# Blaster.net
KiCad netlist of a schematic drawn in EasyEDA Pro
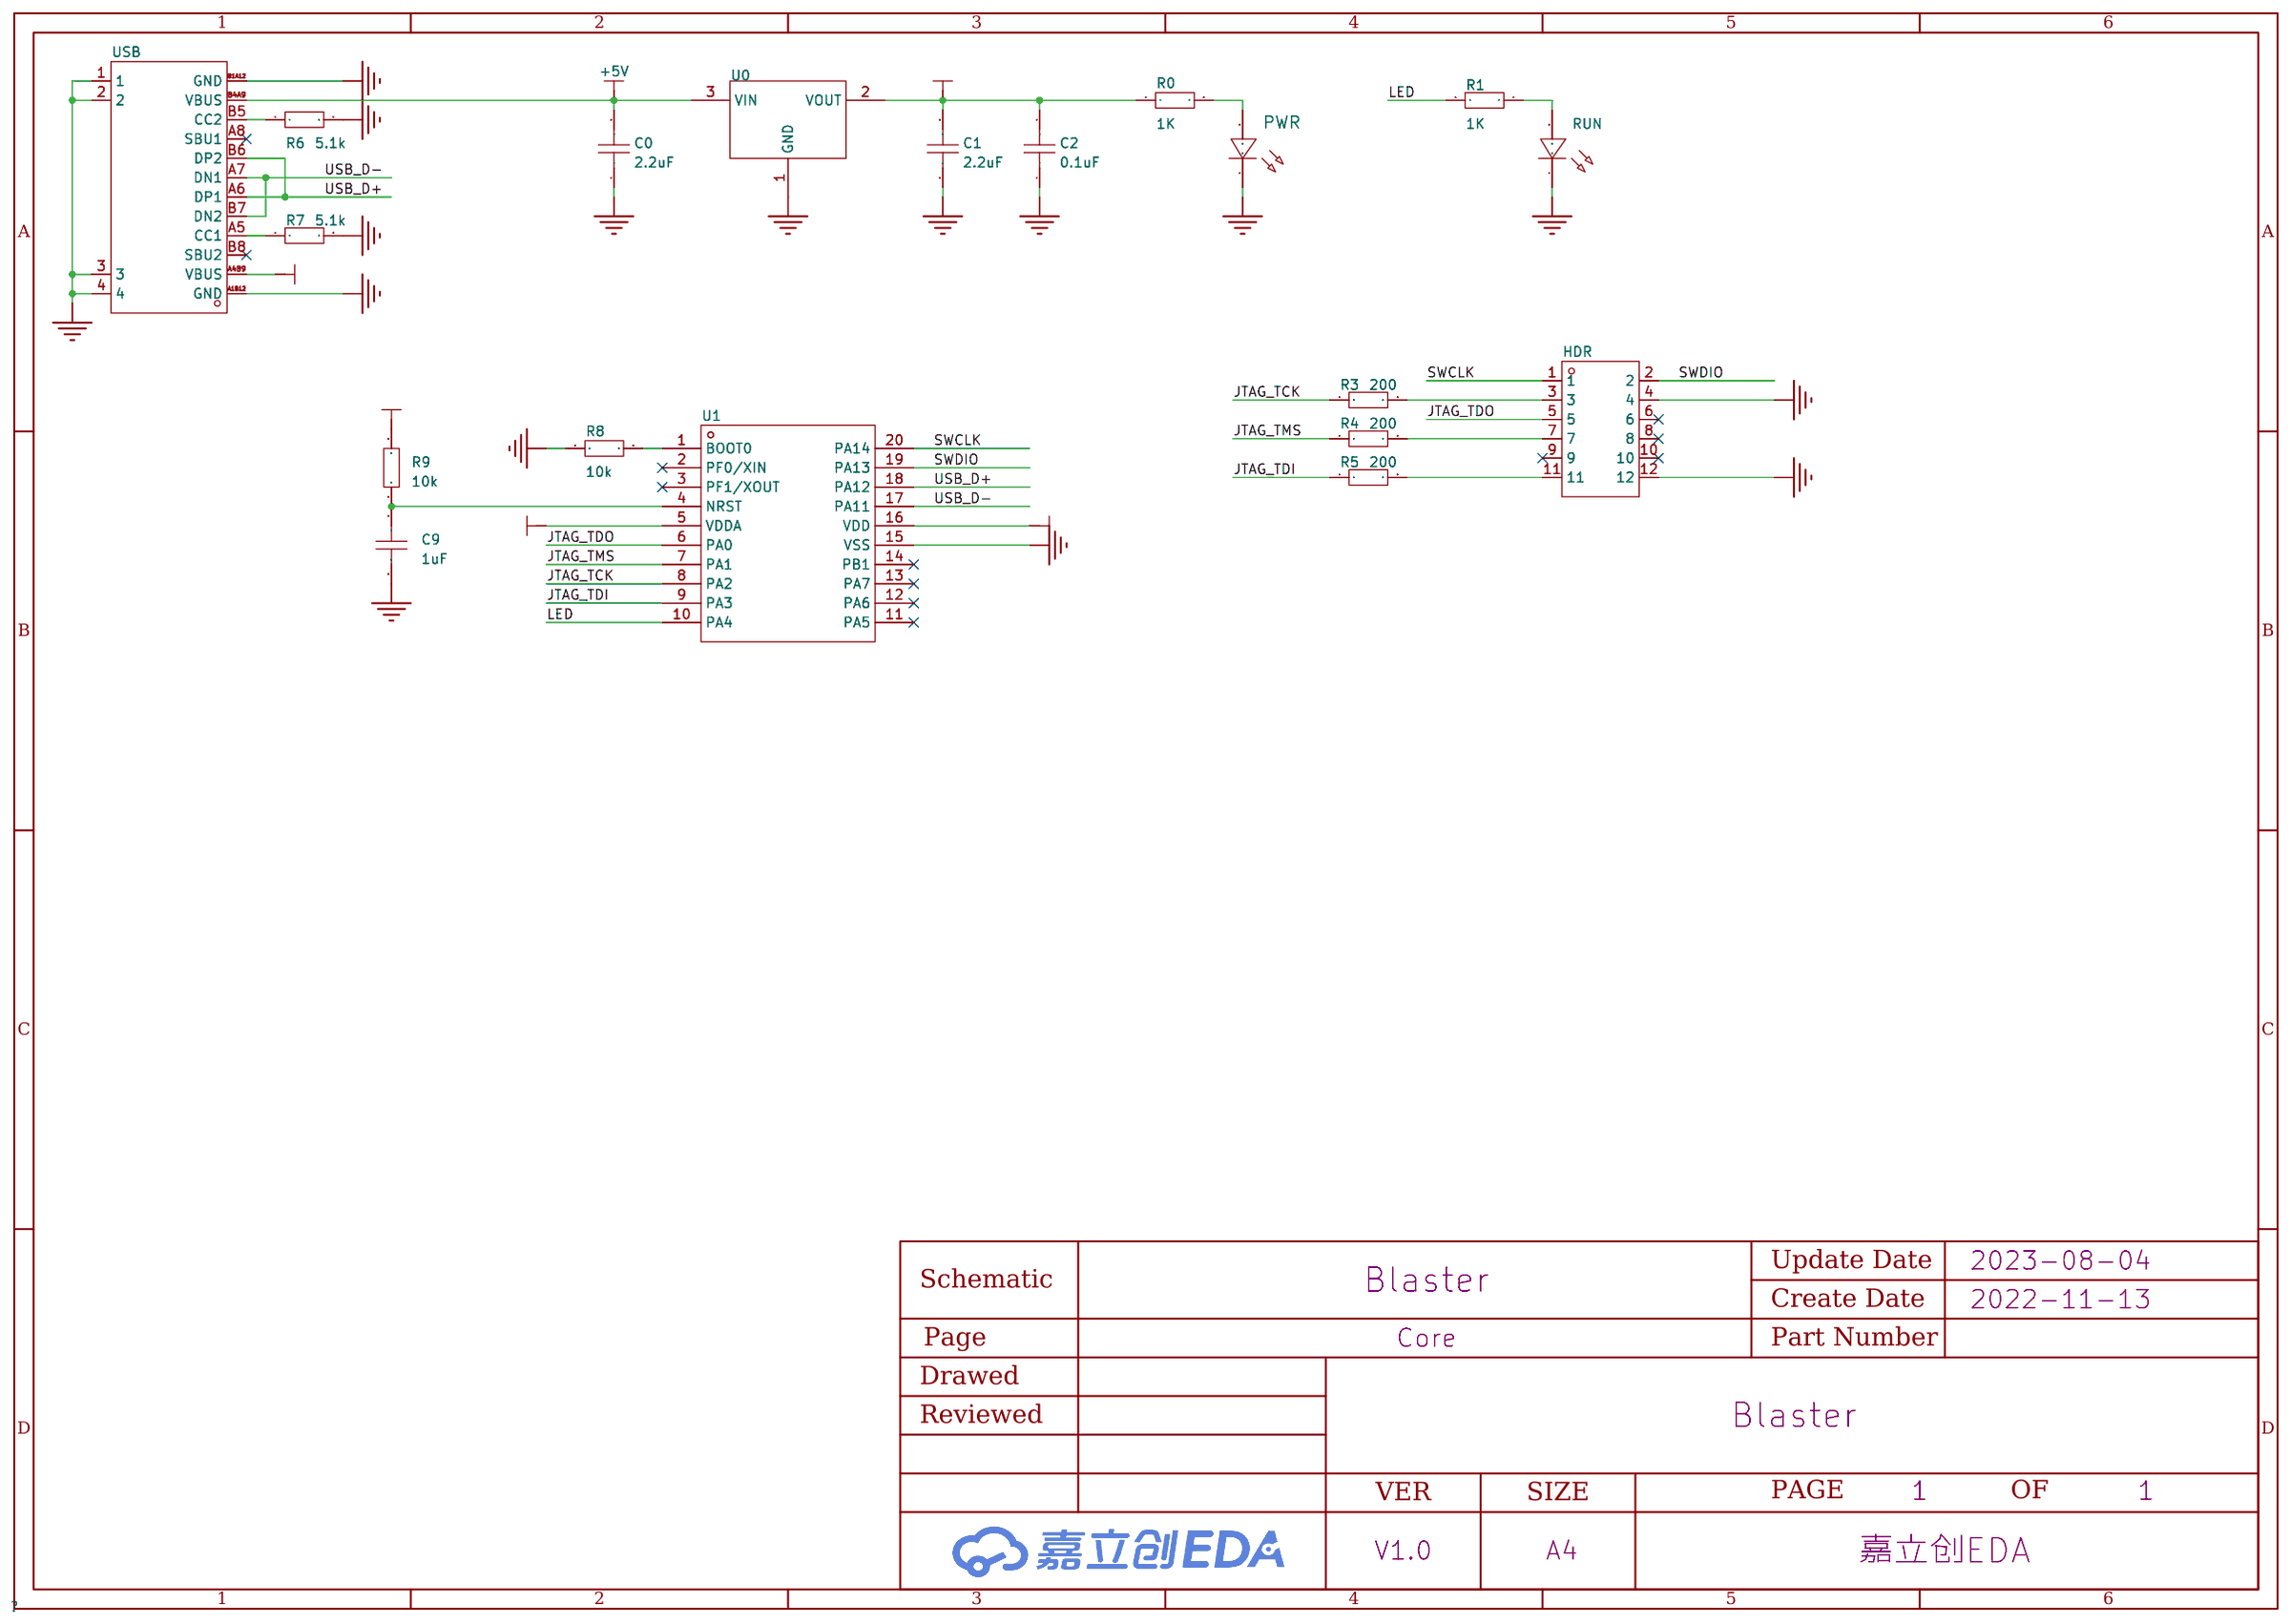
[diagram p0: schematic sheet]

(export (version "E")
  (design (tool "Eeschema 10.0.6"))
  (components
    (comp (ref "C0")
      (value "2.2uF")
      (footprint "easyedapro:C0603")
      (description "容值:100nF;精度:±10%;额定电压:50V;温度系数:X7R;")
      (libsource (lib "easyedapro") (part "C1210X7R475K630NT"))
    )
    (comp (ref "C1")
      (value "2.2uF")
      (footprint "easyedapro:C0603")
      (description "容值:100nF;精度:±10%;额定电压:50V;温度系数:X7R;")
      (libsource (lib "easyedapro") (part "C1210X7R475K630NT"))
    )
    (comp (ref "C2")
      (value "0.1uF")
      (footprint "easyedapro:C0603")
      (description "容值:100nF;精度:±10%;额定电压:50V;温度系数:X7R;")
      (libsource (lib "easyedapro") (part "C1210X7R475K630NT"))
    )
    (comp (ref "C9")
      (value "1uF")
      (footprint "easyedapro:C0603")
      (description "容值:100nF;精度:±10%;额定电压:50V;温度系数:X7R;")
      (libsource (lib "easyedapro") (part "C1210X7R475K630NT"))
    )
    (comp (ref "HDR")
      (value "~")
      (footprint "easyedapro:HDR-SMD_2X6P-P2.54")
      (libsource (lib "easyedapro") (part "HDR-M-2.54_2x6"))
    )
    (comp (ref "PWR")
      (value "~")
      (footprint "easyedapro:LED0603-RD_BLUE")
      (libsource (lib "easyedapro") (part "LED_R"))
    )
    (comp (ref "R0") (value "1K") (footprint "easyedapro:R0603") (libsource (lib "easyedapro") (part "电阻")))
    (comp (ref "R1") (value "1K") (footprint "easyedapro:R0603") (libsource (lib "easyedapro") (part "电阻")))
    (comp (ref "R3") (value "200") (footprint "easyedapro:R0603") (libsource (lib "easyedapro") (part "电阻")))
    (comp (ref "R4") (value "200") (footprint "easyedapro:R0603") (libsource (lib "easyedapro") (part "电阻")))
    (comp (ref "R5") (value "200") (footprint "easyedapro:R0603") (libsource (lib "easyedapro") (part "电阻")))
    (comp (ref "R6") (value "5.1k") (footprint "easyedapro:R0603") (libsource (lib "easyedapro") (part "电阻")))
    (comp (ref "R7") (value "5.1k") (footprint "easyedapro:R0603") (libsource (lib "easyedapro") (part "电阻")))
    (comp (ref "R8") (value "10k") (footprint "easyedapro:R0603") (libsource (lib "easyedapro") (part "电阻")))
    (comp (ref "R9") (value "10k") (footprint "easyedapro:R0603") (libsource (lib "easyedapro") (part "电阻")))
    (comp (ref "RUN")
      (value "~")
      (footprint "easyedapro:LED0603-RD")
      (description "照明颜色:翠绿;色温 - CCT（K）:-;主波长/色坐标:520~535nm;")
      (libsource (lib "easyedapro") (part "LED_G"))
    )
    (comp (ref "U0")
      (value "HT7233")
      (footprint "easyedapro:SOT-23-3_L2.9-W1.6-P1.90-LS2.8-BR")
      (fields (field (name "Manufacturer") "HOLTEK(台湾合泰/盛群)"))
      (libsource (lib "easyedapro") (part "HT7233"))
    )
    (comp (ref "U1")
      (value "~")
      (footprint "easyedapro:TSSOP-20_L6.5-W4.4-P0.65-LS6.4-BL")
      (libsource (lib "easyedapro") (part "AT32F425F8"))
    )
    (comp (ref "USB")
      (value "USB-TYPE-C-017")
      (footprint "easyedapro:USB-TYPE-C-SMD_C9900008089")
      (description "连接器类型:Type-C;标准:-;公母:母座;触点数量:16;端口数量:1;安装方式:卧贴;额定电流 - 电源:3A;工作温度范围:-25~+85;")
      (fields (field (name "Manufacturer") "DEALON(德艺隆)"))
      (libsource (lib "easyedapro") (part "USB-TYPE-C-017"))
    )
  )
  (nets
    (net (code "1") (name "+3.3V") (class "Default")
      (node (ref "C1") (pin "2") (pinfunction "2_2") (pintype "input"))
      (node (ref "C2") (pin "2") (pinfunction "2_2") (pintype "input"))
      (node (ref "R0") (pin "1") (pinfunction "1_1") (pintype "input"))
      (node (ref "R9") (pin "2") (pinfunction "2_2") (pintype "input"))
      (node (ref "U0") (pin "2") (pinfunction "VOUT_2") (pintype "input"))
      (node (ref "U1") (pin "16") (pinfunction "VDD_16") (pintype "input"))
      (node (ref "U1") (pin "5") (pinfunction "VDDA_5") (pintype "input"))
    )
    (net (code "2") (name "+5V") (class "Default")
      (node (ref "C0") (pin "2") (pinfunction "2_2") (pintype "input"))
      (node (ref "U0") (pin "3") (pinfunction "VIN_3") (pintype "input"))
      (node (ref "USB") (pin "A4B9") (pinfunction "VBUS_A4B9") (pintype "input"))
      (node (ref "USB") (pin "B4A9") (pinfunction "VBUS_B4A9") (pintype "input"))
    )
    (net (code "3") (name "/JTAG_TCK") (class "Default")
      (node (ref "R3") (pin "1") (pinfunction "1_1") (pintype "input"))
      (node (ref "U1") (pin "8") (pinfunction "PA2_8") (pintype "input"))
    )
    (net (code "4") (name "/JTAG_TDI") (class "Default")
      (node (ref "R5") (pin "1") (pinfunction "1_1") (pintype "input"))
      (node (ref "U1") (pin "9") (pinfunction "PA3_9") (pintype "input"))
    )
    (net (code "5") (name "/JTAG_TDO") (class "Default")
      (node (ref "HDR") (pin "5") (pinfunction "5_5") (pintype "input"))
      (node (ref "U1") (pin "6") (pinfunction "PA0_6") (pintype "input"))
    )
    (net (code "6") (name "/JTAG_TMS") (class "Default")
      (node (ref "R4") (pin "1") (pinfunction "1_1") (pintype "input"))
      (node (ref "U1") (pin "7") (pinfunction "PA1_7") (pintype "input"))
    )
    (net (code "7") (name "/LED") (class "Default")
      (node (ref "R1") (pin "2") (pinfunction "2_2") (pintype "input"))
      (node (ref "U1") (pin "10") (pinfunction "PA4_10") (pintype "input"))
    )
    (net (code "8") (name "/SWCLK") (class "Default")
      (node (ref "HDR") (pin "1") (pinfunction "1_1") (pintype "input"))
      (node (ref "U1") (pin "20") (pinfunction "PA14_20") (pintype "input"))
    )
    (net (code "9") (name "/SWDIO") (class "Default")
      (node (ref "HDR") (pin "2") (pinfunction "2_2") (pintype "input"))
      (node (ref "U1") (pin "19") (pinfunction "PA13_19") (pintype "input"))
    )
    (net (code "10") (name "/USB_D+") (class "Default")
      (node (ref "U1") (pin "18") (pinfunction "PA12_18") (pintype "input"))
      (node (ref "USB") (pin "A6") (pinfunction "DP1_A6") (pintype "input"))
      (node (ref "USB") (pin "B6") (pinfunction "DP2_B6") (pintype "input"))
    )
    (net (code "11") (name "/USB_D-") (class "Default")
      (node (ref "U1") (pin "17") (pinfunction "PA11_17") (pintype "input"))
      (node (ref "USB") (pin "A7") (pinfunction "DN1_A7") (pintype "input"))
      (node (ref "USB") (pin "B7") (pinfunction "DN2_B7") (pintype "input"))
    )
    (net (code "12") (name "GND") (class "Default")
      (node (ref "C0") (pin "1") (pinfunction "1_1") (pintype "input"))
      (node (ref "C1") (pin "1") (pinfunction "1_1") (pintype "input"))
      (node (ref "C2") (pin "1") (pinfunction "1_1") (pintype "input"))
      (node (ref "C9") (pin "2") (pinfunction "2_2") (pintype "input"))
      (node (ref "HDR") (pin "12") (pinfunction "12_12") (pintype "input"))
      (node (ref "HDR") (pin "4") (pinfunction "4_4") (pintype "input"))
      (node (ref "PWR") (pin "1") (pinfunction "C_1") (pintype "input"))
      (node (ref "R6") (pin "2") (pinfunction "2_2") (pintype "input"))
      (node (ref "R7") (pin "2") (pinfunction "2_2") (pintype "input"))
      (node (ref "R8") (pin "1") (pinfunction "1_1") (pintype "input"))
      (node (ref "RUN") (pin "1") (pinfunction "C_1") (pintype "input"))
      (node (ref "U0") (pin "1") (pinfunction "GND_1") (pintype "input"))
      (node (ref "U1") (pin "15") (pinfunction "VSS_15") (pintype "input"))
      (node (ref "USB") (pin "1") (pinfunction "1_1") (pintype "input"))
      (node (ref "USB") (pin "2") (pinfunction "2_2") (pintype "input"))
      (node (ref "USB") (pin "3") (pinfunction "3_3") (pintype "input"))
      (node (ref "USB") (pin "4") (pinfunction "4_4") (pintype "input"))
      (node (ref "USB") (pin "A1B12") (pinfunction "GND_A1B12") (pintype "input"))
      (node (ref "USB") (pin "B1A12") (pinfunction "GND_B1A12") (pintype "input"))
    )
    (net (code "13") (name "Net-(HDR-Pad3)") (class "Default")
      (node (ref "HDR") (pin "3") (pinfunction "3_3") (pintype "input"))
      (node (ref "R3") (pin "2") (pinfunction "2_2") (pintype "input"))
    )
    (net (code "14") (name "Net-(HDR-Pad7)") (class "Default")
      (node (ref "HDR") (pin "7") (pinfunction "7_7") (pintype "input"))
      (node (ref "R4") (pin "2") (pinfunction "2_2") (pintype "input"))
    )
    (net (code "15") (name "Net-(HDR-Pad11)") (class "Default")
      (node (ref "HDR") (pin "11") (pinfunction "11_11") (pintype "input"))
      (node (ref "R5") (pin "2") (pinfunction "2_2") (pintype "input"))
    )
    (net (code "16") (name "Net-(PWR-A)") (class "Default")
      (node (ref "PWR") (pin "2") (pinfunction "A_2") (pintype "input"))
      (node (ref "R0") (pin "2") (pinfunction "2_2") (pintype "input"))
    )
    (net (code "17") (name "Net-(RUN-A)") (class "Default")
      (node (ref "R1") (pin "1") (pinfunction "1_1") (pintype "input"))
      (node (ref "RUN") (pin "2") (pinfunction "A_2") (pintype "input"))
    )
    (net (code "18") (name "Net-(U1-BOOT0)") (class "Default")
      (node (ref "R8") (pin "2") (pinfunction "2_2") (pintype "input"))
      (node (ref "U1") (pin "1") (pinfunction "BOOT0_1") (pintype "input"))
    )
    (net (code "19") (name "Net-(U1-NRST)") (class "Default")
      (node (ref "C9") (pin "1") (pinfunction "1_1") (pintype "input"))
      (node (ref "R9") (pin "1") (pinfunction "1_1") (pintype "input"))
      (node (ref "U1") (pin "4") (pinfunction "NRST_4") (pintype "input"))
    )
    (net (code "20") (name "Net-(USB-CC1)") (class "Default")
      (node (ref "R7") (pin "1") (pinfunction "1_1") (pintype "input"))
      (node (ref "USB") (pin "A5") (pinfunction "CC1_A5") (pintype "input"))
    )
    (net (code "21") (name "Net-(USB-CC2)") (class "Default")
      (node (ref "R6") (pin "1") (pinfunction "1_1") (pintype "input"))
      (node (ref "USB") (pin "B5") (pinfunction "CC2_B5") (pintype "input"))
    )
    (net (code "22") (name "unconnected-(HDR-Pad6)") (class "Default")
      (node (ref "HDR") (pin "6") (pinfunction "6_6") (pintype "input+no_connect"))
    )
    (net (code "23") (name "unconnected-(HDR-Pad8)") (class "Default")
      (node (ref "HDR") (pin "8") (pinfunction "8_8") (pintype "input+no_connect"))
    )
    (net (code "24") (name "unconnected-(HDR-Pad9)") (class "Default")
      (node (ref "HDR") (pin "9") (pinfunction "9_9") (pintype "input+no_connect"))
    )
    (net (code "25") (name "unconnected-(HDR-Pad10)") (class "Default")
      (node (ref "HDR") (pin "10") (pinfunction "10_10") (pintype "input+no_connect"))
    )
    (net (code "26") (name "unconnected-(U1-PA5-Pad11)") (class "Default")
      (node (ref "U1") (pin "11") (pinfunction "PA5_11") (pintype "input+no_connect"))
    )
    (net (code "27") (name "unconnected-(U1-PA6-Pad12)") (class "Default")
      (node (ref "U1") (pin "12") (pinfunction "PA6_12") (pintype "input+no_connect"))
    )
    (net (code "28") (name "unconnected-(U1-PA7-Pad13)") (class "Default")
      (node (ref "U1") (pin "13") (pinfunction "PA7_13") (pintype "input+no_connect"))
    )
    (net (code "29") (name "unconnected-(U1-PB1-Pad14)") (class "Default")
      (node (ref "U1") (pin "14") (pinfunction "PB1_14") (pintype "input+no_connect"))
    )
    (net (code "30") (name "unconnected-(U1-PF0{slash}XIN-Pad2)") (class "Default")
      (node (ref "U1") (pin "2") (pinfunction "PF0/XIN_2") (pintype "input+no_connect"))
    )
    (net (code "31") (name "unconnected-(U1-PF1{slash}XOUT-Pad3)") (class "Default")
      (node (ref "U1") (pin "3") (pinfunction "PF1/XOUT_3") (pintype "input+no_connect"))
    )
    (net (code "32") (name "unconnected-(USB-SBU1-PadA8)") (class "Default")
      (node (ref "USB") (pin "A8") (pinfunction "SBU1_A8") (pintype "input+no_connect"))
    )
    (net (code "33") (name "unconnected-(USB-SBU2-PadB8)") (class "Default")
      (node (ref "USB") (pin "B8") (pinfunction "SBU2_B8") (pintype "input+no_connect"))
    )
  )
)
